# Connectors_and_USB.net
KiCad netlist of a schematic drawn in Altium Designer
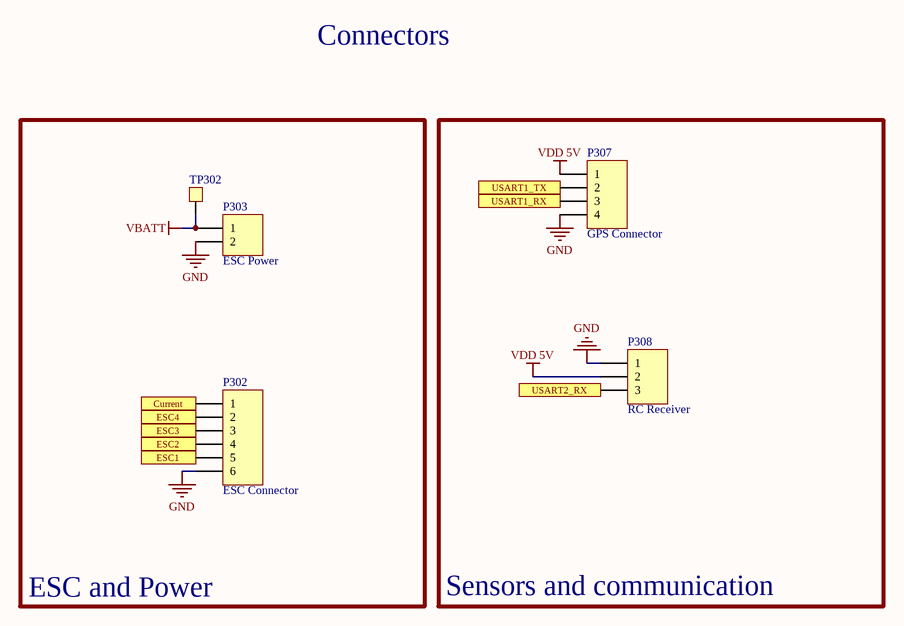
[diagram p0: Connectors and USB.SchDoc]

(export (version "E")
  (design (tool "Eeschema 10.0.6"))
  (components
    (comp (ref "P302")
      (value "ESC Connector")
      (footprint "B6B-XH-A")
      (description "Header, 6-Pin")
      (fields (field (name "PUBLISHER") "Altium Limited"))
      (libsource (lib "Miscellaneous Connectors") (part "Header 6"))
    )
    (comp (ref "P303")
      (value "ESC Power")
      (footprint "HDR1X2")
      (description "Header, 2-Pin")
      (fields (field (name "PUBLISHER") "Altium Limited"))
      (libsource (lib "Miscellaneous Connectors") (part "Header 2"))
    )
    (comp (ref "P307")
      (value "GPS Connector")
      (footprint "B4B-XH-A")
      (description "Header, 4-Pin")
      (fields (field (name "PUBLISHER") "Altium Limited"))
      (libsource (lib "Miscellaneous Connectors") (part "Header 4"))
    )
    (comp (ref "P308")
      (value "RC Receiver")
      (footprint "B3B-XH-A")
      (description "Header, 3-Pin")
      (fields (field (name "PUBLISHER") "Altium Limited"))
      (libsource (lib "Miscellaneous Connectors") (part "Header 3"))
    )
    (comp (ref "TP302")
      (value "Test Point")
      (footprint "Test Point THT 1mm")
      (libsource (lib "FYP_Drone") (part "Test Point"))
    )
  )
  (nets
    (net (code "1") (name "/Current") (class "Default")
      (node (ref "P302") (pin "1") (pinfunction "1_1") (pintype "passive"))
    )
    (net (code "2") (name "/ESC1") (class "Default")
      (node (ref "P302") (pin "5") (pinfunction "5_5") (pintype "passive"))
    )
    (net (code "3") (name "/ESC2") (class "Default")
      (node (ref "P302") (pin "4") (pinfunction "4_4") (pintype "passive"))
    )
    (net (code "4") (name "/ESC3") (class "Default")
      (node (ref "P302") (pin "3") (pinfunction "3_3") (pintype "passive"))
    )
    (net (code "5") (name "/ESC4") (class "Default")
      (node (ref "P302") (pin "2") (pinfunction "2_2") (pintype "passive"))
    )
    (net (code "6") (name "/USART1_RX") (class "Default")
      (node (ref "P307") (pin "3") (pinfunction "3_3") (pintype "passive"))
    )
    (net (code "7") (name "/USART1_TX") (class "Default")
      (node (ref "P307") (pin "2") (pinfunction "2_2") (pintype "passive"))
    )
    (net (code "8") (name "/USART2_RX") (class "Default")
      (node (ref "P308") (pin "3") (pinfunction "3_3") (pintype "passive"))
    )
    (net (code "9") (name "GND") (class "Default")
      (node (ref "P302") (pin "6") (pinfunction "6_6") (pintype "passive"))
      (node (ref "P303") (pin "2") (pinfunction "2_2") (pintype "passive"))
      (node (ref "P307") (pin "4") (pinfunction "4_4") (pintype "passive"))
      (node (ref "P308") (pin "1") (pinfunction "1_1") (pintype "passive"))
    )
    (net (code "10") (name "VBATT") (class "Default")
      (node (ref "P303") (pin "1") (pinfunction "1_1") (pintype "passive"))
      (node (ref "TP302") (pin "1") (pintype "passive"))
    )
    (net (code "11") (name "VDD 5V") (class "Default")
      (node (ref "P307") (pin "1") (pinfunction "1_1") (pintype "passive"))
      (node (ref "P308") (pin "2") (pinfunction "2_2") (pintype "passive"))
    )
  )
)
